# Controlled_Voltage_Gain.net
KiCad netlist of a schematic drawn in Altium Designer
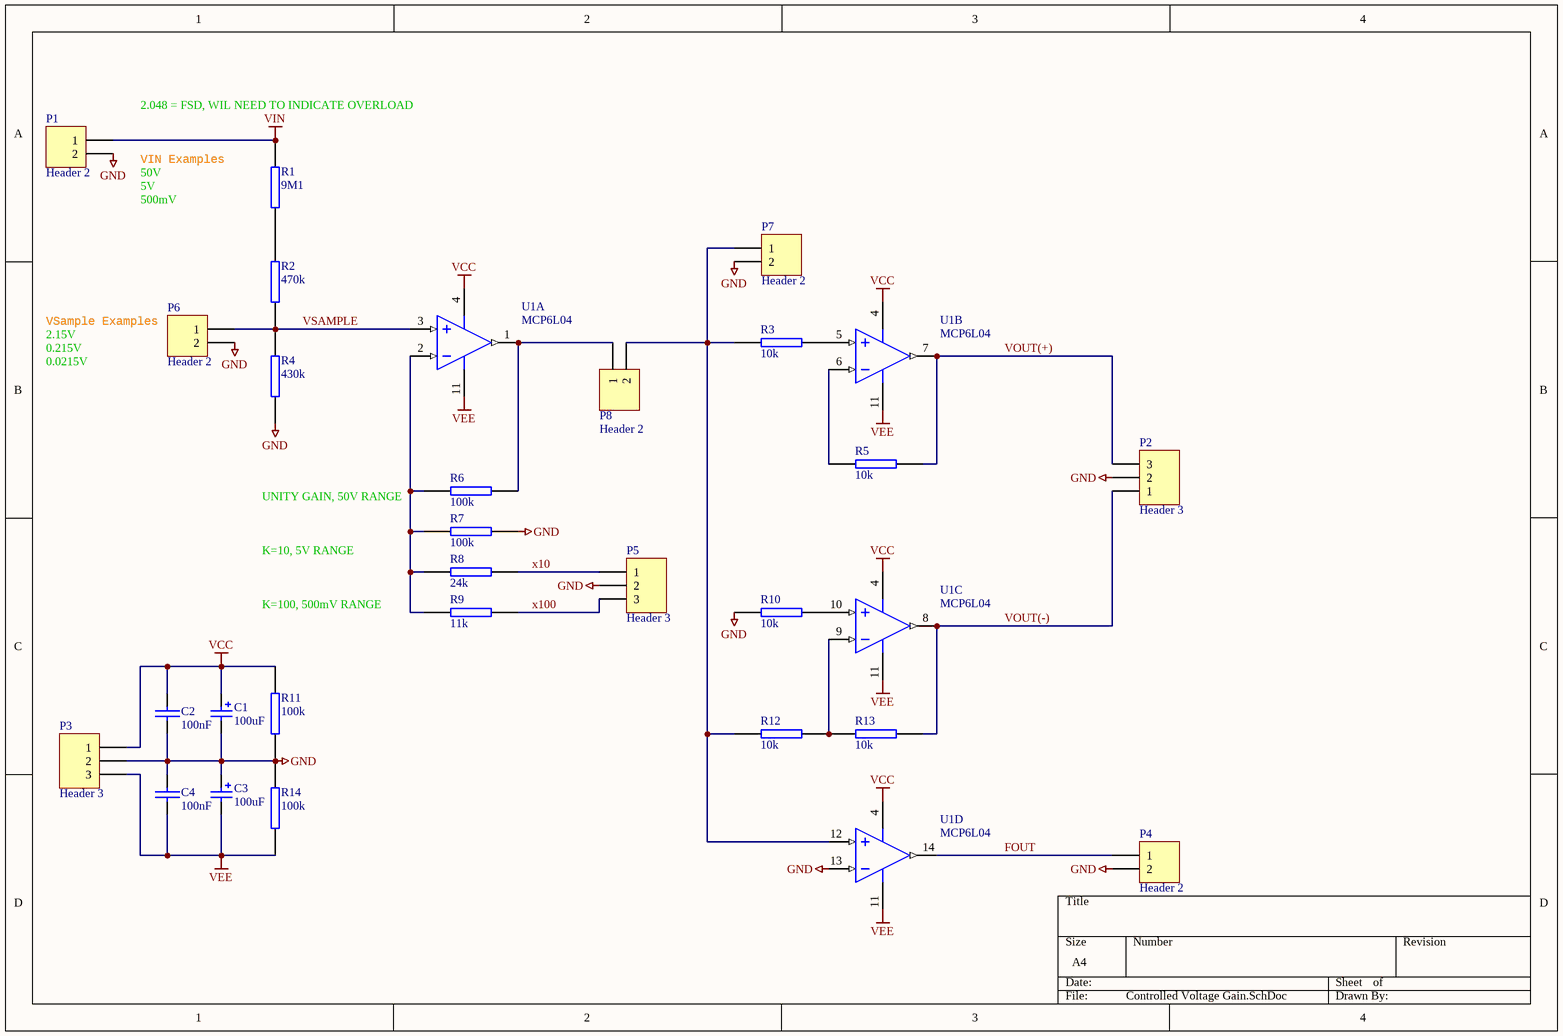
[diagram p0: Controlled Voltage Gain.SchDoc]

(export (version "E")
  (design (tool "Eeschema 10.0.6"))
  (components
    (comp (ref "C1")
      (value "100uF")
      (footprint "RB5-10.5")
      (description "CAPACITOR POLARISED TAG B CASE")
      (fields
        (field (name "MANUFACTURER") "Generic Components")
        (field (name "MOUSER PART NO.") "74-293D106X9020B8T")
      )
      (libsource (lib "Mi-Call Schematic") (part "Cap Pol"))
    )
    (comp (ref "C2")
      (value "100nF")
      (footprint "CAP (3D) - 0603")
      (description "CAPACITOR SMD 0603")
      (fields (field (name "MOUSER PART NO.") "81-GCM188R71C104KA7D") (field (name "MANUFACTURER") "Murata"))
      (libsource (lib "Mi-Call Schematic") (part "CAP"))
    )
    (comp (ref "C3")
      (value "100uF")
      (footprint "RB5-10.5")
      (description "CAPACITOR POLARISED TAG B CASE")
      (fields
        (field (name "MANUFACTURER") "Generic Components")
        (field (name "MOUSER PART NO.") "74-293D106X9020B8T")
      )
      (libsource (lib "Mi-Call Schematic") (part "Cap Pol"))
    )
    (comp (ref "C4")
      (value "100nF")
      (footprint "CAP (3D) - 0603")
      (description "CAPACITOR SMD 0603")
      (fields (field (name "MOUSER PART NO.") "81-GCM188R71C104KA7D") (field (name "MANUFACTURER") "Murata"))
      (libsource (lib "Mi-Call Schematic") (part "CAP"))
    )
    (comp (ref "P1")
      (value "Header 2")
      (footprint "HDR1X2")
      (description "Header, 2-Pin")
      (fields (field (name "PUBLISHER") "Altium Limited"))
      (libsource (lib "Miscellaneous Connectors") (part "Header 2"))
    )
    (comp (ref "P2")
      (value "Header 3")
      (footprint "HDR1X3")
      (description "Header, 3-Pin")
      (fields (field (name "PUBLISHER") "Altium Limited"))
      (libsource (lib "Miscellaneous Connectors") (part "Header 3"))
    )
    (comp (ref "P3")
      (value "Header 3")
      (footprint "HDR1X3")
      (description "Header, 3-Pin")
      (fields (field (name "PUBLISHER") "Altium Limited"))
      (libsource (lib "") (part "Header 3_1"))
    )
    (comp (ref "P4")
      (value "Header 2")
      (footprint "HDR1X2")
      (description "Header, 2-Pin")
      (fields (field (name "PUBLISHER") "Altium Limited"))
      (libsource (lib "") (part "Header 2_1"))
    )
    (comp (ref "P5")
      (value "Header 3")
      (footprint "HDR1X3")
      (description "Header, 3-Pin")
      (fields (field (name "PUBLISHER") "Altium Limited"))
      (libsource (lib "") (part "Header 3_2"))
    )
    (comp (ref "P6")
      (value "Header 2")
      (footprint "HDR1X2")
      (description "Header, 2-Pin")
      (fields (field (name "PUBLISHER") "Altium Limited"))
      (libsource (lib "Miscellaneous Connectors") (part "Header 2"))
    )
    (comp (ref "P7")
      (value "Header 2")
      (footprint "HDR1X2")
      (description "Header, 2-Pin")
      (fields (field (name "PUBLISHER") "Altium Limited"))
      (libsource (lib "") (part "Header 2_1"))
    )
    (comp (ref "P8")
      (value "Header 2")
      (footprint "HDR1X2")
      (description "Header, 2-Pin")
      (fields (field (name "PUBLISHER") "Altium Limited"))
      (libsource (lib "") (part "Header 2_2"))
    )
    (comp (ref "R1")
      (value "9M1")
      (footprint "RES (3D) - 0603")
      (description "RESISTOR SMD 0603 10k")
      (fields
        (field (name "MOUSER PART NO.") "71-CRCW0603-8.06M-E3")
        (field (name "MANUFACTURER") "Vishay/Dale")
      )
      (libsource (lib "NASCO Resistors") (part "RES SMD 0603 10k"))
    )
    (comp (ref "R2")
      (value "470k")
      (footprint "RES (3D) - 0603")
      (description "RESISTOR SMD 0603 10k")
      (fields
        (field (name "MOUSER PART NO.") "Vishay/Dale")
        (field (name "MANUFACTURER") "71-CRCW0603-1.62M-E3")
      )
      (libsource (lib "NASCO Resistors") (part "RES SMD 0603 10k"))
    )
    (comp (ref "R3")
      (value "10k")
      (footprint "RES (3D) - 0603")
      (description "RESISTOR SMD 0603 10k")
      (fields (field (name "MOUSER PART NO.") "652-CR0603FX-1002ELF") (field (name "MANUFACTURER") "Bourns"))
      (libsource (lib "NASCO Resistors") (part "RES SMD 0603 10k"))
    )
    (comp (ref "R4")
      (value "430k")
      (footprint "RES (3D) - 0603")
      (description "RESISTOR SMD 0603 10k")
      (fields
        (field (name "MOUSER PART NO.") "Vishay/Dale")
        (field (name "MANUFACTURER") "71-CRCW0603-1.62M-E3")
      )
      (libsource (lib "NASCO Resistors") (part "RES SMD 0603 10k"))
    )
    (comp (ref "R5")
      (value "10k")
      (footprint "RES (3D) - 0603")
      (description "RESISTOR SMD 0603 10k")
      (fields (field (name "MOUSER PART NO.") "652-CR0603FX-1002ELF") (field (name "MANUFACTURER") "Bourns"))
      (libsource (lib "NASCO Resistors") (part "RES SMD 0603 10k"))
    )
    (comp (ref "R6")
      (value "100k")
      (footprint "RES (3D) - 0603")
      (description "RESISTOR SMD 0603 10k")
      (fields (field (name "MOUSER PART NO.") "652-CR0603FX-1002ELF") (field (name "MANUFACTURER") "Bourns"))
      (libsource (lib "NASCO Resistors") (part "RES SMD 0603 10k"))
    )
    (comp (ref "R7")
      (value "100k")
      (footprint "RES (3D) - 0603")
      (description "RESISTOR SMD 0603 10k")
      (fields (field (name "MOUSER PART NO.") "652-CR0603FX-1002ELF") (field (name "MANUFACTURER") "Bourns"))
      (libsource (lib "NASCO Resistors") (part "RES SMD 0603 10k"))
    )
    (comp (ref "R8")
      (value "24k")
      (footprint "RES (3D) - 0603")
      (description "RESISTOR SMD 0603 10k")
      (fields (field (name "MOUSER PART NO.") "652-CR0603FX-1002ELF") (field (name "MANUFACTURER") "Bourns"))
      (libsource (lib "NASCO Resistors") (part "RES SMD 0603 10k"))
    )
    (comp (ref "R9")
      (value "11k")
      (footprint "RES (3D) - 0603")
      (description "RESISTOR SMD 0603 10k")
      (fields (field (name "MOUSER PART NO.") "652-CR0603FX-1002ELF") (field (name "MANUFACTURER") "Bourns"))
      (libsource (lib "NASCO Resistors") (part "RES SMD 0603 10k"))
    )
    (comp (ref "R10")
      (value "10k")
      (footprint "RES (3D) - 0603")
      (description "RESISTOR SMD 0603 10k")
      (fields (field (name "MOUSER PART NO.") "652-CR0603FX-1002ELF") (field (name "MANUFACTURER") "Bourns"))
      (libsource (lib "NASCO Resistors") (part "RES SMD 0603 10k"))
    )
    (comp (ref "R11")
      (value "100k")
      (footprint "RES (3D) - 0603")
      (description "RESISTOR SMD 0603 10k")
      (fields (field (name "MOUSER PART NO.") "652-CR0603FX-1002ELF") (field (name "MANUFACTURER") "Bourns"))
      (libsource (lib "NASCO Resistors") (part "RES SMD 0603 10k"))
    )
    (comp (ref "R12")
      (value "10k")
      (footprint "RES (3D) - 0603")
      (description "RESISTOR SMD 0603 10k")
      (fields (field (name "MOUSER PART NO.") "652-CR0603FX-1002ELF") (field (name "MANUFACTURER") "Bourns"))
      (libsource (lib "NASCO Resistors") (part "RES SMD 0603 10k"))
    )
    (comp (ref "R13")
      (value "10k")
      (footprint "RES (3D) - 0603")
      (description "RESISTOR SMD 0603 10k")
      (fields (field (name "MOUSER PART NO.") "652-CR0603FX-1002ELF") (field (name "MANUFACTURER") "Bourns"))
      (libsource (lib "NASCO Resistors") (part "RES SMD 0603 10k"))
    )
    (comp (ref "R14")
      (value "100k")
      (footprint "RES (3D) - 0603")
      (description "RESISTOR SMD 0603 10k")
      (fields (field (name "MOUSER PART NO.") "652-CR0603FX-1002ELF") (field (name "MANUFACTURER") "Bourns"))
      (libsource (lib "NASCO Resistors") (part "RES SMD 0603 10k"))
    )
    (comp (ref "U1")
      (value "MCP6L04")
      (footprint "SO-14")
      (libsource (lib "Microchip Opamps") (part "MCP6L04"))
    )
  )
  (nets
    (net (code "1") (name "/FOUT") (class "Default")
      (node (ref "P4") (pin "1") (pinfunction "1_1") (pintype "passive"))
      (node (ref "U1") (pin "14") (pinfunction "OUTD_14") (pintype "output"))
    )
    (net (code "2") (name "/VOUT(+)") (class "Default")
      (node (ref "P2") (pin "3") (pinfunction "3_3") (pintype "passive"))
      (node (ref "R5") (pin "2") (pinfunction "2_2") (pintype "passive"))
      (node (ref "U1") (pin "7") (pinfunction "OUTB_7") (pintype "output"))
    )
    (net (code "3") (name "/VOUT(-)") (class "Default")
      (node (ref "P2") (pin "1") (pinfunction "1_1") (pintype "passive"))
      (node (ref "R13") (pin "2") (pinfunction "2_2") (pintype "passive"))
      (node (ref "U1") (pin "8") (pinfunction "OUTC_8") (pintype "output"))
    )
    (net (code "4") (name "/VSAMPLE") (class "Default")
      (node (ref "P6") (pin "1") (pinfunction "1_1") (pintype "passive"))
      (node (ref "R2") (pin "2") (pinfunction "2_2") (pintype "passive"))
      (node (ref "R4") (pin "1") (pinfunction "1_1") (pintype "passive"))
      (node (ref "U1") (pin "3") (pinfunction "INA+_3") (pintype "input"))
    )
    (net (code "5") (name "/x10") (class "Default")
      (node (ref "P5") (pin "1") (pinfunction "1_1") (pintype "passive"))
      (node (ref "R8") (pin "1") (pinfunction "1_1") (pintype "passive"))
    )
    (net (code "6") (name "/x100") (class "Default")
      (node (ref "P5") (pin "3") (pinfunction "3_3") (pintype "passive"))
      (node (ref "R9") (pin "1") (pinfunction "1_1") (pintype "passive"))
    )
    (net (code "7") (name "GND") (class "Default")
      (node (ref "C1") (pin "2") (pinfunction "2_2") (pintype "passive"))
      (node (ref "C2") (pin "2") (pinfunction "2_2") (pintype "passive"))
      (node (ref "C3") (pin "1") (pinfunction "1_1") (pintype "passive"))
      (node (ref "C4") (pin "1") (pinfunction "1_1") (pintype "passive"))
      (node (ref "P1") (pin "2") (pinfunction "2_2") (pintype "passive"))
      (node (ref "P2") (pin "2") (pinfunction "2_2") (pintype "passive"))
      (node (ref "P3") (pin "2") (pinfunction "2_2") (pintype "passive"))
      (node (ref "P4") (pin "2") (pinfunction "2_2") (pintype "passive"))
      (node (ref "P5") (pin "2") (pinfunction "2_2") (pintype "passive"))
      (node (ref "P6") (pin "2") (pinfunction "2_2") (pintype "passive"))
      (node (ref "P7") (pin "2") (pinfunction "2_2") (pintype "passive"))
      (node (ref "R10") (pin "1") (pinfunction "1_1") (pintype "passive"))
      (node (ref "R11") (pin "1") (pinfunction "1_1") (pintype "passive"))
      (node (ref "R14") (pin "2") (pinfunction "2_2") (pintype "passive"))
      (node (ref "R4") (pin "2") (pinfunction "2_2") (pintype "passive"))
      (node (ref "R7") (pin "1") (pinfunction "1_1") (pintype "passive"))
      (node (ref "U1") (pin "13") (pinfunction "INC-_13") (pintype "input"))
    )
    (net (code "8") (name "Net-(R1-Pad1)") (class "Default")
      (node (ref "R1") (pin "1") (pinfunction "1_1") (pintype "passive"))
      (node (ref "R2") (pin "1") (pinfunction "1_1") (pintype "passive"))
    )
    (net (code "9") (name "Net-(U1A-INA-)") (class "Default")
      (node (ref "R6") (pin "2") (pinfunction "2_2") (pintype "passive"))
      (node (ref "R7") (pin "2") (pinfunction "2_2") (pintype "passive"))
      (node (ref "R8") (pin "2") (pinfunction "2_2") (pintype "passive"))
      (node (ref "R9") (pin "2") (pinfunction "2_2") (pintype "passive"))
      (node (ref "U1") (pin "2") (pinfunction "INA-_2") (pintype "input"))
    )
    (net (code "10") (name "Net-(U1A-OUTA)") (class "Default")
      (node (ref "P8") (pin "1") (pinfunction "1_1") (pintype "passive"))
      (node (ref "R6") (pin "1") (pinfunction "1_1") (pintype "passive"))
      (node (ref "U1") (pin "1") (pinfunction "OUTA_1") (pintype "output"))
    )
    (net (code "11") (name "Net-(U1B-INB+)") (class "Default")
      (node (ref "R3") (pin "2") (pinfunction "2_2") (pintype "passive"))
      (node (ref "U1") (pin "5") (pinfunction "INB+_5") (pintype "input"))
    )
    (net (code "12") (name "Net-(U1B-INB-)") (class "Default")
      (node (ref "R5") (pin "1") (pinfunction "1_1") (pintype "passive"))
      (node (ref "U1") (pin "6") (pinfunction "INB-_6") (pintype "input"))
    )
    (net (code "13") (name "Net-(U1C-INC+)") (class "Default")
      (node (ref "R10") (pin "2") (pinfunction "2_2") (pintype "passive"))
      (node (ref "U1") (pin "10") (pinfunction "INC+_10") (pintype "input"))
    )
    (net (code "14") (name "Net-(U1C-INC-)") (class "Default")
      (node (ref "R12") (pin "2") (pinfunction "2_2") (pintype "passive"))
      (node (ref "R13") (pin "1") (pinfunction "1_1") (pintype "passive"))
      (node (ref "U1") (pin "9") (pinfunction "INC-_9") (pintype "input"))
    )
    (net (code "15") (name "Net-(U1D-INC+)") (class "Default")
      (node (ref "P7") (pin "1") (pinfunction "1_1") (pintype "passive"))
      (node (ref "P8") (pin "2") (pinfunction "2_2") (pintype "passive"))
      (node (ref "R12") (pin "1") (pinfunction "1_1") (pintype "passive"))
      (node (ref "R3") (pin "1") (pinfunction "1_1") (pintype "passive"))
      (node (ref "U1") (pin "12") (pinfunction "INC+_12") (pintype "input"))
    )
    (net (code "16") (name "VCC") (class "Default")
      (node (ref "C1") (pin "1") (pinfunction "1_1") (pintype "passive"))
      (node (ref "C2") (pin "1") (pinfunction "1_1") (pintype "passive"))
      (node (ref "P3") (pin "1") (pinfunction "1_1") (pintype "passive"))
      (node (ref "R11") (pin "2") (pinfunction "2_2") (pintype "passive"))
      (node (ref "U1") (pin "4") (pinfunction "VDD_4") (pintype "power_in"))
    )
    (net (code "17") (name "VEE") (class "Default")
      (node (ref "C3") (pin "2") (pinfunction "2_2") (pintype "passive"))
      (node (ref "C4") (pin "2") (pinfunction "2_2") (pintype "passive"))
      (node (ref "P3") (pin "3") (pinfunction "3_3") (pintype "passive"))
      (node (ref "R14") (pin "1") (pinfunction "1_1") (pintype "passive"))
      (node (ref "U1") (pin "11") (pinfunction "VSS_11") (pintype "power_in"))
    )
    (net (code "18") (name "VIN") (class "Default")
      (node (ref "P1") (pin "1") (pinfunction "1_1") (pintype "passive"))
      (node (ref "R1") (pin "2") (pinfunction "2_2") (pintype "passive"))
    )
  )
)
